# SCH_Fume-Extractor_2025-12-03.net
KiCad netlist of a schematic drawn in EasyEDA
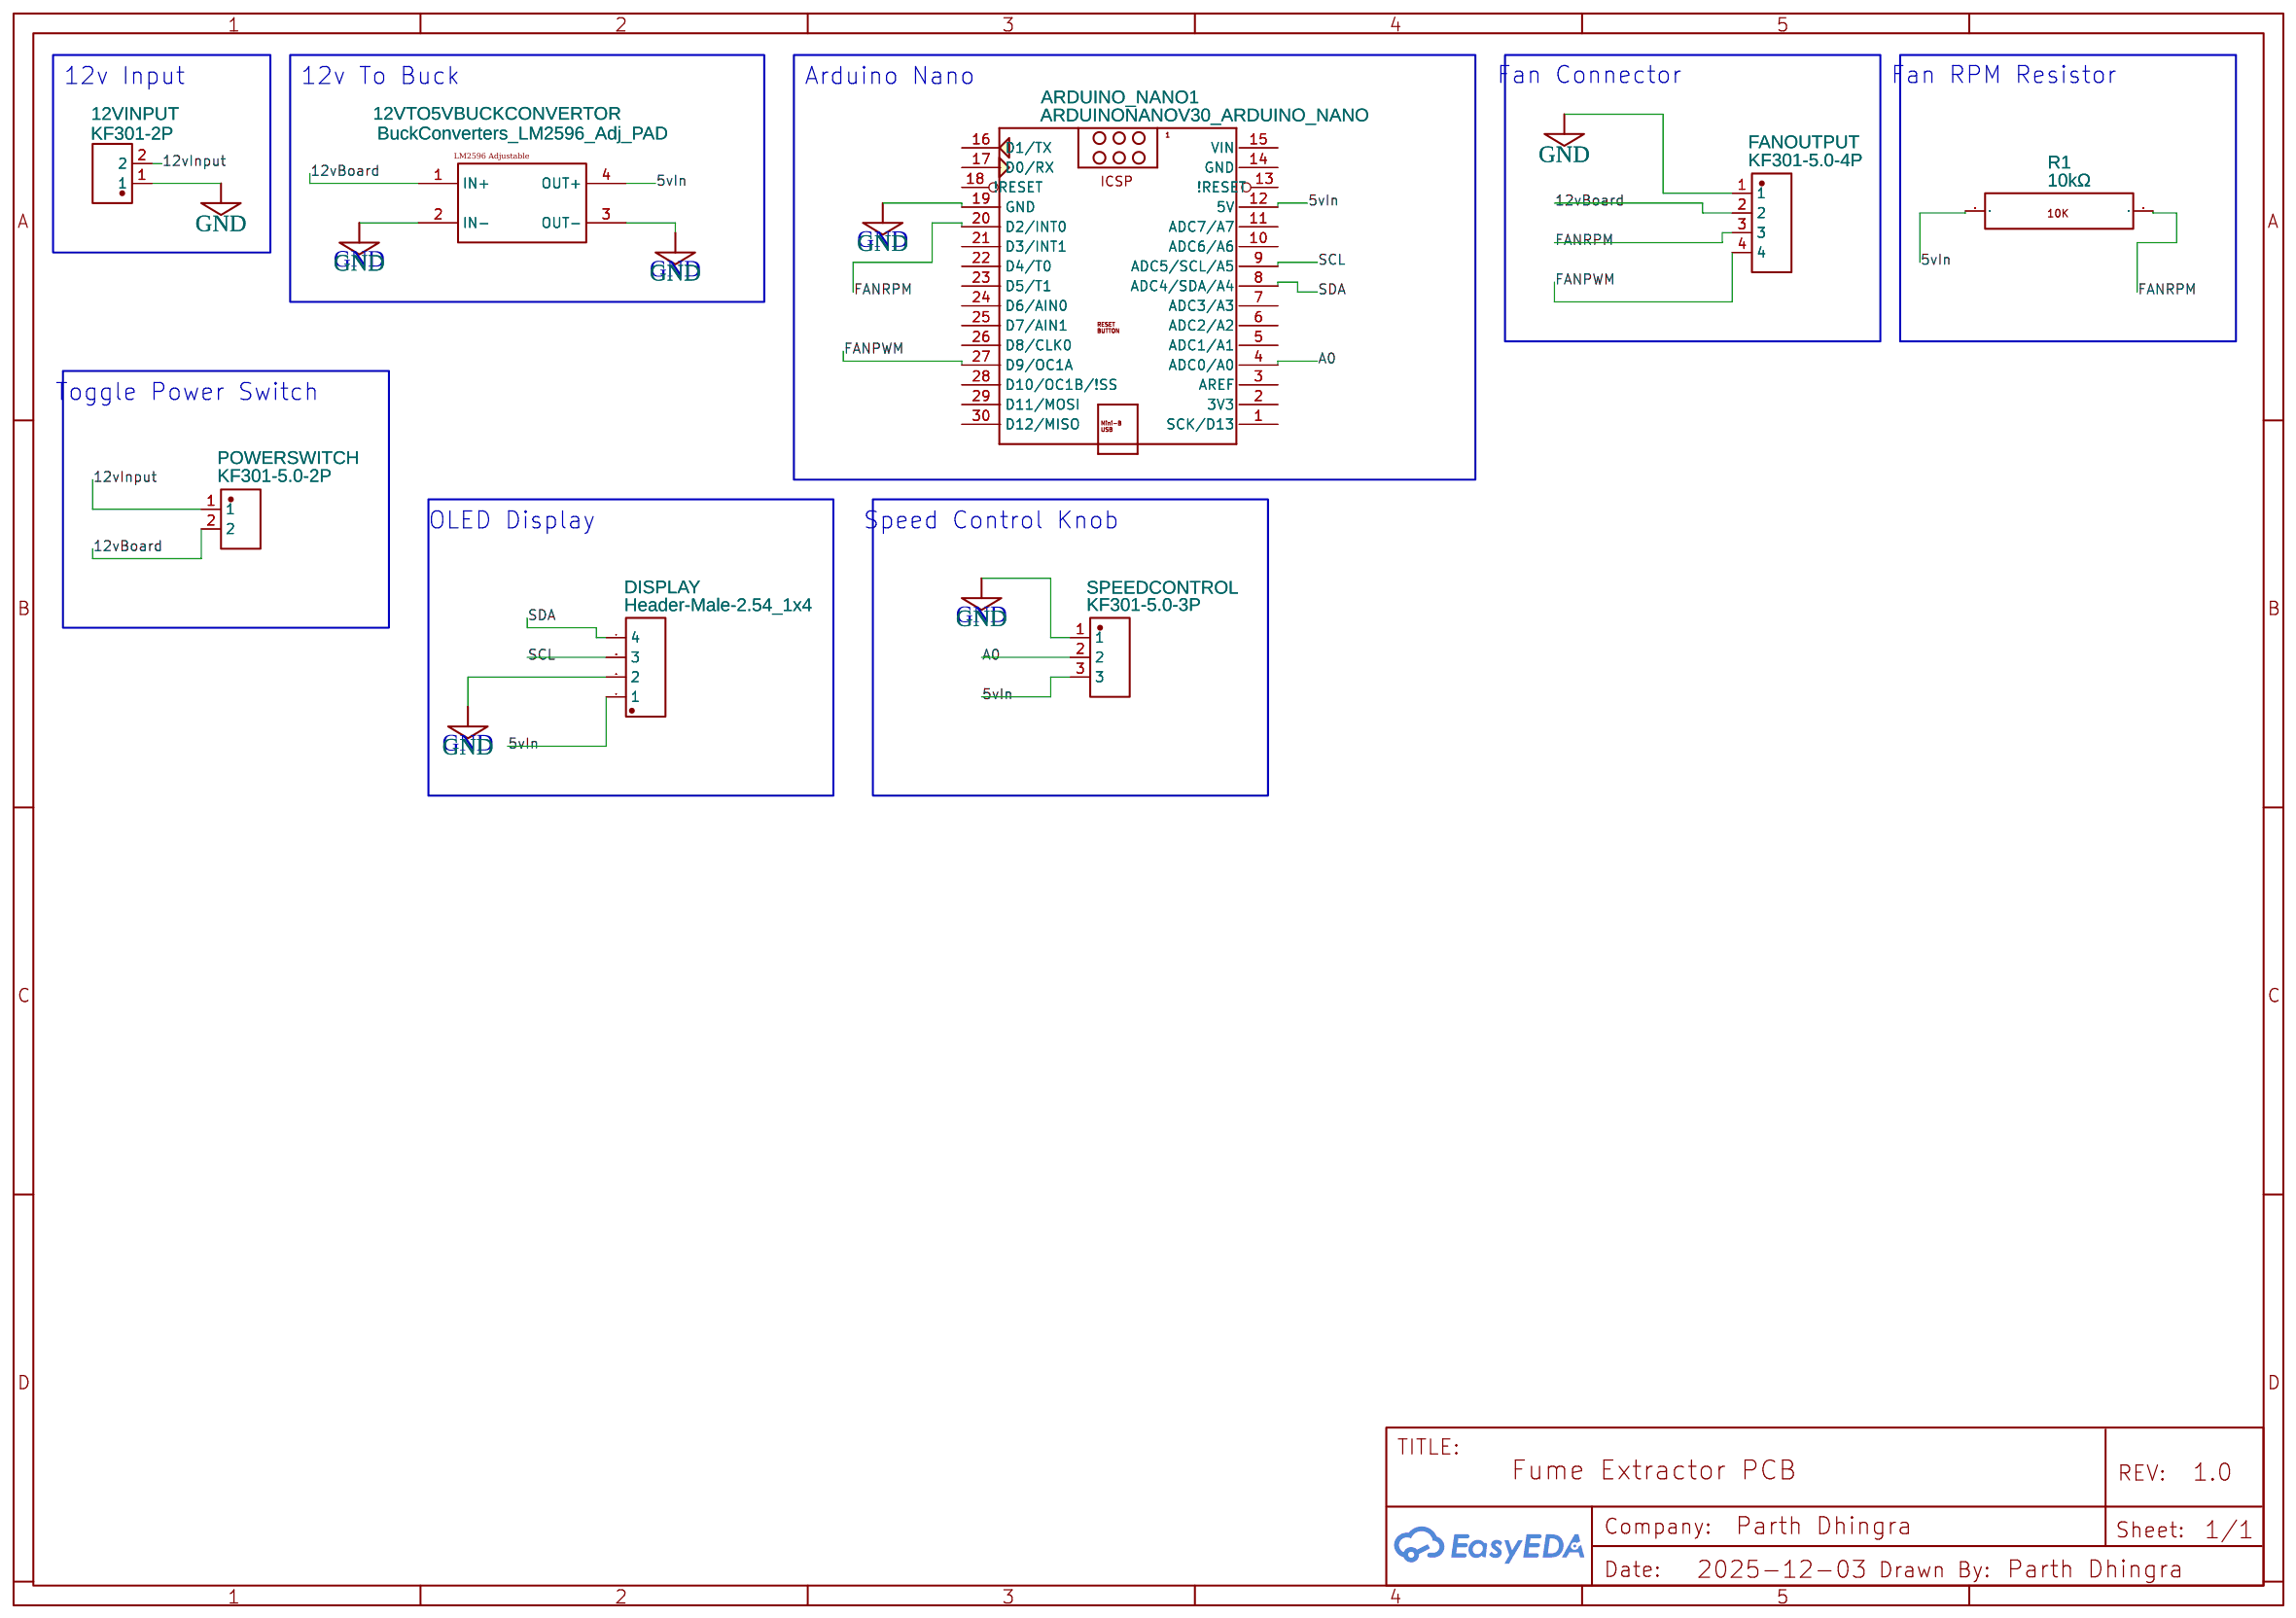
[diagram p0: schematic sheet]

(export (version "E")
  (design (tool "Eeschema 10.0.6"))
  (components
    (comp (ref "12VINPUT")
      (value "KF301-2P")
      (fields (field (name "Manufacturer Part") "KF301-2P接线端子"))
      (libsource (lib "") (part "KF301-2P接线端子"))
    )
    (comp (ref "12VTO5VBUCKCONVERTOR")
      (value "BuckConverters_LM2596_Adj_PAD")
      (libsource (lib "") (part "BuckConverters_LM2596_Adj_PAD"))
    )
    (comp (ref "ARDUINO_NANO1")
      (value "ARDUINONANOV30_ARDUINO_NANO")
      (libsource (lib "") (part "ARDUINONANOV30_ARDUINO_NANO"))
    )
    (comp (ref "DISPLAY")
      (value "Header-Male-2.54_1x4")
      (fields
        (field (name "Manufacturer Part") "210S-1*4P L=11.6MMGold-plated black")
        (field (name "Manufacturer") "Ckmtw")
      )
      (libsource (lib "") (part "Header-Male-2.54_1x4"))
    )
    (comp (ref "FANOUTPUT")
      (value "KF301-5.0-4P")
      (fields
        (field (name "Manufacturer Part") "DB128V-5.0-4P-GN-S")
        (field (name "Manufacturer") "DORABO(地博电气)")
      )
      (libsource (lib "") (part "KF301-5.0-4P"))
    )
    (comp (ref "POWERSWITCH")
      (value "KF301-5.0-2P")
      (fields (field (name "Manufacturer") "KEFA(科发)"))
      (libsource (lib "") (part "KF301-5.0-2P"))
    )
    (comp (ref "R1")
      (value "10kΩ")
      (fields (field (name "Manufacturer Part") "MF1/4W-10KΩ±1% T") (field (name "Manufacturer") "CCO(千志电子)"))
      (libsource (lib "") (part "SYMBOL--XX--RESISTOR-1/4W-10K-1-PERCENT HJN"))
    )
    (comp (ref "SPEEDCONTROL")
      (value "KF301-5.0-3P")
      (fields (field (name "Manufacturer") "KEFA(科发)"))
      (libsource (lib "") (part "KF301-5.0-3P"))
    )
  )
  (nets
    (net (code "1") (name "/5vIn") (class "Default")
      (node (ref "12VTO5VBUCKCONVERTOR") (pin "4") (pinfunction "OUT+_4") (pintype "unspecified"))
      (node (ref "ARDUINO_NANO1") (pin "12") (pinfunction "5V_12") (pintype "bidirectional"))
      (node (ref "DISPLAY") (pin "1") (pinfunction "1_1") (pintype "unspecified"))
      (node (ref "R1") (pin "1") (pinfunction "1_1") (pintype "unspecified"))
      (node (ref "SPEEDCONTROL") (pin "3") (pinfunction "3_3") (pintype "unspecified"))
    )
    (net (code "2") (name "/12vBoard") (class "Default")
      (node (ref "12VTO5VBUCKCONVERTOR") (pin "1") (pinfunction "IN+_1") (pintype "unspecified"))
      (node (ref "FANOUTPUT") (pin "2") (pinfunction "2_2") (pintype "unspecified"))
      (node (ref "POWERSWITCH") (pin "2") (pinfunction "2_2") (pintype "unspecified"))
    )
    (net (code "3") (name "/12vInput") (class "Default")
      (node (ref "12VINPUT") (pin "2") (pinfunction "2_2") (pintype "unspecified"))
      (node (ref "POWERSWITCH") (pin "1") (pinfunction "1_1") (pintype "unspecified"))
    )
    (net (code "4") (name "/A0") (class "Default")
      (node (ref "ARDUINO_NANO1") (pin "4") (pinfunction "ADC0/A0_4") (pintype "bidirectional"))
      (node (ref "SPEEDCONTROL") (pin "2") (pinfunction "2_2") (pintype "unspecified"))
    )
    (net (code "5") (name "/FANPWM") (class "Default")
      (node (ref "ARDUINO_NANO1") (pin "27") (pinfunction "D9/OC1A_27") (pintype "bidirectional"))
      (node (ref "FANOUTPUT") (pin "4") (pinfunction "4_4") (pintype "unspecified"))
    )
    (net (code "6") (name "/FANRPM") (class "Default")
      (node (ref "ARDUINO_NANO1") (pin "20") (pinfunction "D2/INT0_20") (pintype "bidirectional"))
      (node (ref "FANOUTPUT") (pin "3") (pinfunction "3_3") (pintype "unspecified"))
      (node (ref "R1") (pin "2") (pinfunction "2_2") (pintype "unspecified"))
    )
    (net (code "7") (name "/SCL") (class "Default")
      (node (ref "ARDUINO_NANO1") (pin "9") (pinfunction "ADC5/SCL/A5_9") (pintype "bidirectional"))
      (node (ref "DISPLAY") (pin "3") (pinfunction "3_3") (pintype "unspecified"))
    )
    (net (code "8") (name "/SDA") (class "Default")
      (node (ref "ARDUINO_NANO1") (pin "8") (pinfunction "ADC4/SDA/A4_8") (pintype "bidirectional"))
      (node (ref "DISPLAY") (pin "4") (pinfunction "4_4") (pintype "unspecified"))
    )
    (net (code "9") (name "GND") (class "Default")
      (node (ref "12VINPUT") (pin "1") (pinfunction "1_1") (pintype "unspecified"))
      (node (ref "12VTO5VBUCKCONVERTOR") (pin "2") (pinfunction "IN-_2") (pintype "unspecified"))
      (node (ref "12VTO5VBUCKCONVERTOR") (pin "3") (pinfunction "OUT-_3") (pintype "unspecified"))
      (node (ref "ARDUINO_NANO1") (pin "19") (pinfunction "GND_19") (pintype "bidirectional"))
      (node (ref "DISPLAY") (pin "2") (pinfunction "2_2") (pintype "unspecified"))
      (node (ref "FANOUTPUT") (pin "1") (pinfunction "1_1") (pintype "unspecified"))
      (node (ref "SPEEDCONTROL") (pin "1") (pinfunction "1_1") (pintype "unspecified"))
    )
    (net (code "10") (name "unconnected-(ARDUINO_NANO1-!RESET-Pad13)") (class "Default")
      (node (ref "ARDUINO_NANO1") (pin "13") (pinfunction "!RESET_13") (pintype "bidirectional"))
    )
    (net (code "11") (name "unconnected-(ARDUINO_NANO1-!RESET-Pad18)") (class "Default")
      (node (ref "ARDUINO_NANO1") (pin "18") (pinfunction "!RESET_18") (pintype "bidirectional"))
    )
    (net (code "12") (name "unconnected-(ARDUINO_NANO1-3V3-Pad2)") (class "Default")
      (node (ref "ARDUINO_NANO1") (pin "2") (pinfunction "3V3_2") (pintype "bidirectional"))
    )
    (net (code "13") (name "unconnected-(ARDUINO_NANO1-ADC1{slash}A1-Pad5)") (class "Default")
      (node (ref "ARDUINO_NANO1") (pin "5") (pinfunction "ADC1/A1_5") (pintype "bidirectional"))
    )
    (net (code "14") (name "unconnected-(ARDUINO_NANO1-ADC2{slash}A2-Pad6)") (class "Default")
      (node (ref "ARDUINO_NANO1") (pin "6") (pinfunction "ADC2/A2_6") (pintype "bidirectional"))
    )
    (net (code "15") (name "unconnected-(ARDUINO_NANO1-ADC3{slash}A3-Pad7)") (class "Default")
      (node (ref "ARDUINO_NANO1") (pin "7") (pinfunction "ADC3/A3_7") (pintype "bidirectional"))
    )
    (net (code "16") (name "unconnected-(ARDUINO_NANO1-ADC6{slash}A6-Pad10)") (class "Default")
      (node (ref "ARDUINO_NANO1") (pin "10") (pinfunction "ADC6/A6_10") (pintype "bidirectional"))
    )
    (net (code "17") (name "unconnected-(ARDUINO_NANO1-ADC7{slash}A7-Pad11)") (class "Default")
      (node (ref "ARDUINO_NANO1") (pin "11") (pinfunction "ADC7/A7_11") (pintype "bidirectional"))
    )
    (net (code "18") (name "unconnected-(ARDUINO_NANO1-AREF-Pad3)") (class "Default")
      (node (ref "ARDUINO_NANO1") (pin "3") (pinfunction "AREF_3") (pintype "bidirectional"))
    )
    (net (code "19") (name "unconnected-(ARDUINO_NANO1-D0{slash}RX-Pad17)") (class "Default")
      (node (ref "ARDUINO_NANO1") (pin "17") (pinfunction "D0/RX_17") (pintype "bidirectional"))
    )
    (net (code "20") (name "unconnected-(ARDUINO_NANO1-D1{slash}TX-Pad16)") (class "Default")
      (node (ref "ARDUINO_NANO1") (pin "16") (pinfunction "D1/TX_16") (pintype "bidirectional"))
    )
    (net (code "21") (name "unconnected-(ARDUINO_NANO1-D3{slash}INT1-Pad21)") (class "Default")
      (node (ref "ARDUINO_NANO1") (pin "21") (pinfunction "D3/INT1_21") (pintype "bidirectional"))
    )
    (net (code "22") (name "unconnected-(ARDUINO_NANO1-D4{slash}T0-Pad22)") (class "Default")
      (node (ref "ARDUINO_NANO1") (pin "22") (pinfunction "D4/T0_22") (pintype "bidirectional"))
    )
    (net (code "23") (name "unconnected-(ARDUINO_NANO1-D5{slash}T1-Pad23)") (class "Default")
      (node (ref "ARDUINO_NANO1") (pin "23") (pinfunction "D5/T1_23") (pintype "bidirectional"))
    )
    (net (code "24") (name "unconnected-(ARDUINO_NANO1-D6{slash}AIN0-Pad24)") (class "Default")
      (node (ref "ARDUINO_NANO1") (pin "24") (pinfunction "D6/AIN0_24") (pintype "bidirectional"))
    )
    (net (code "25") (name "unconnected-(ARDUINO_NANO1-D7{slash}AIN1-Pad25)") (class "Default")
      (node (ref "ARDUINO_NANO1") (pin "25") (pinfunction "D7/AIN1_25") (pintype "bidirectional"))
    )
    (net (code "26") (name "unconnected-(ARDUINO_NANO1-D8{slash}CLK0-Pad26)") (class "Default")
      (node (ref "ARDUINO_NANO1") (pin "26") (pinfunction "D8/CLK0_26") (pintype "bidirectional"))
    )
    (net (code "27") (name "unconnected-(ARDUINO_NANO1-D10{slash}OC1B{slash}!SS-Pad28)") (class "Default")
      (node (ref "ARDUINO_NANO1") (pin "28") (pinfunction "D10/OC1B/!SS_28") (pintype "bidirectional"))
    )
    (net (code "28") (name "unconnected-(ARDUINO_NANO1-D11{slash}MOSI-Pad29)") (class "Default")
      (node (ref "ARDUINO_NANO1") (pin "29") (pinfunction "D11/MOSI_29") (pintype "bidirectional"))
    )
    (net (code "29") (name "unconnected-(ARDUINO_NANO1-D12{slash}MISO-Pad30)") (class "Default")
      (node (ref "ARDUINO_NANO1") (pin "30") (pinfunction "D12/MISO_30") (pintype "bidirectional"))
    )
    (net (code "30") (name "unconnected-(ARDUINO_NANO1-GND-Pad14)") (class "Default")
      (node (ref "ARDUINO_NANO1") (pin "14") (pinfunction "GND_14") (pintype "bidirectional"))
    )
    (net (code "31") (name "unconnected-(ARDUINO_NANO1-SCK{slash}D13-Pad1)") (class "Default")
      (node (ref "ARDUINO_NANO1") (pin "1") (pinfunction "SCK/D13_1") (pintype "bidirectional"))
    )
    (net (code "32") (name "unconnected-(ARDUINO_NANO1-VIN-Pad15)") (class "Default")
      (node (ref "ARDUINO_NANO1") (pin "15") (pinfunction "VIN_15") (pintype "bidirectional"))
    )
  )
)
